# sch_cm4_usb.net
KiCad netlist of a schematic drawn in Altium Designer
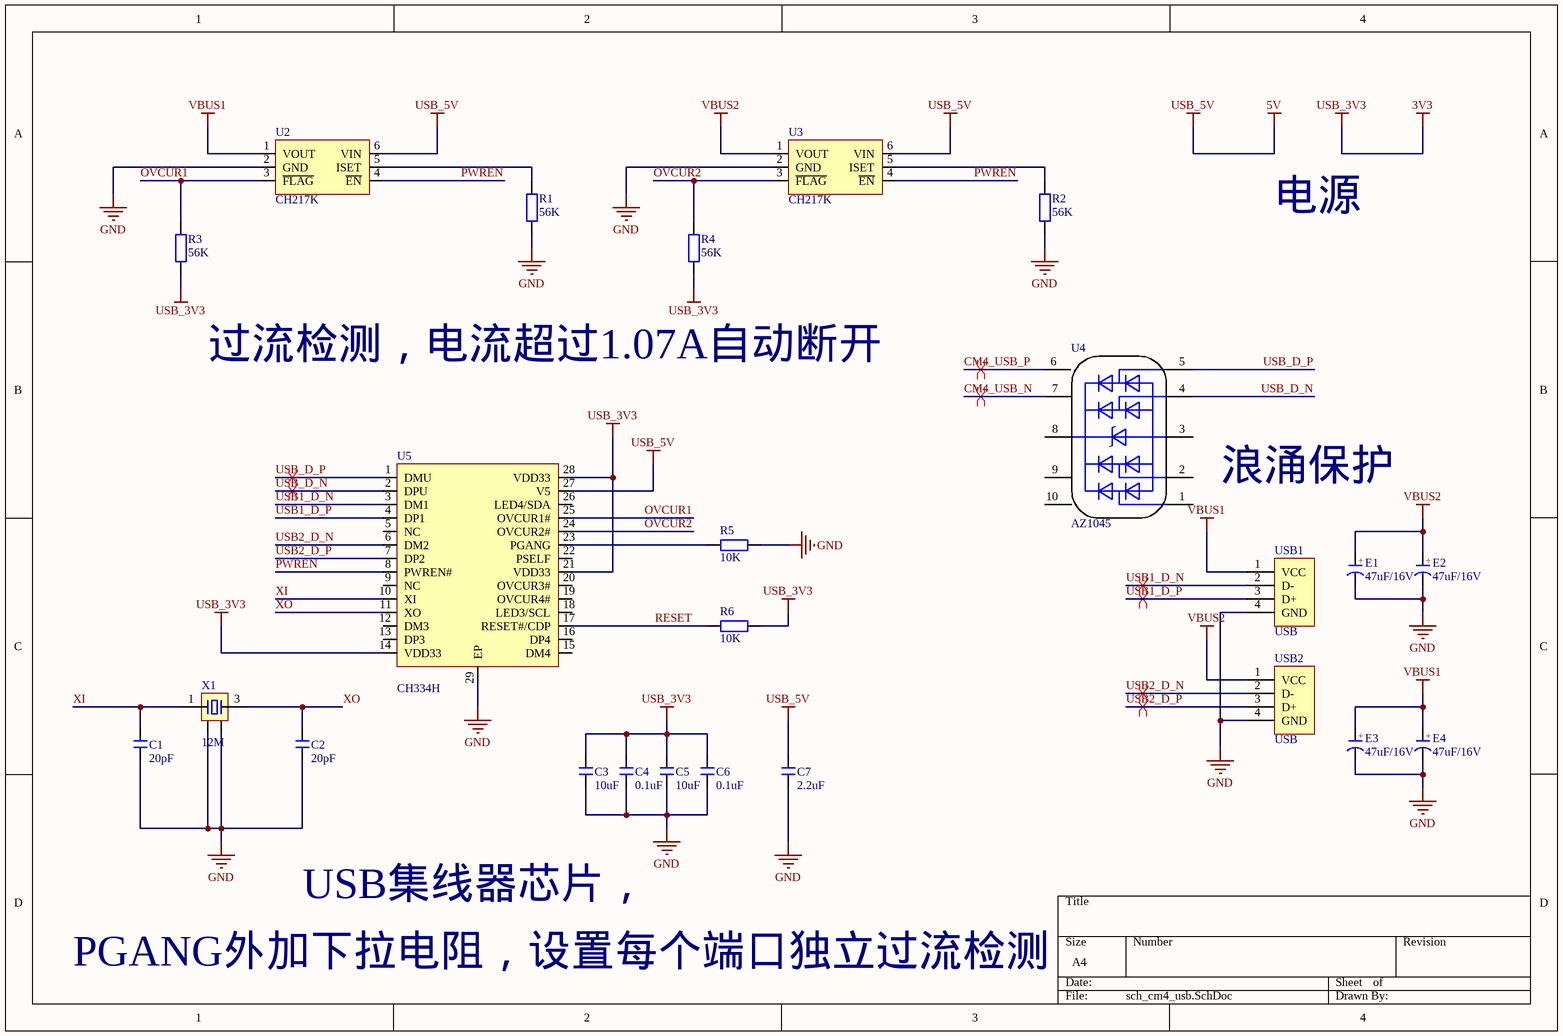
[diagram p0: sch_cm4_usb.SchDoc]

(export (version "E")
  (design (tool "Eeschema 10.0.6"))
  (components
    (comp (ref "C1")
      (value "20pF")
      (footprint "C 0402_L")
      (description "贴片电容")
      (libsource (lib "0.1 - 电阻-电容-电感") (part "C"))
    )
    (comp (ref "C2")
      (value "20pF")
      (footprint "C 0402_L")
      (description "贴片电容")
      (libsource (lib "0.1 - 电阻-电容-电感") (part "C"))
    )
    (comp (ref "C3")
      (value "10uF")
      (footprint "C 0402_L")
      (description "贴片电容")
      (libsource (lib "0.1 - 电阻-电容-电感") (part "C"))
    )
    (comp (ref "C4")
      (value "0.1uF")
      (footprint "C 0402_L")
      (description "贴片电容")
      (libsource (lib "0.1 - 电阻-电容-电感") (part "C"))
    )
    (comp (ref "C5")
      (value "10uF")
      (footprint "C 0402_L")
      (description "贴片电容")
      (libsource (lib "0.1 - 电阻-电容-电感") (part "C"))
    )
    (comp (ref "C6")
      (value "0.1uF")
      (footprint "C 0402_L")
      (description "贴片电容")
      (libsource (lib "0.1 - 电阻-电容-电感") (part "C"))
    )
    (comp (ref "C7")
      (value "2.2uF")
      (footprint "C 0402_L")
      (description "贴片电容")
      (libsource (lib "0.1 - 电阻-电容-电感") (part "C"))
    )
    (comp (ref "E1")
      (value "47uF/16V")
      (footprint "CD B(3528)")
      (description "贴片钽电容")
      (libsource (lib "0.1 - 电阻-电容-电感") (part "CT"))
    )
    (comp (ref "E2")
      (value "47uF/16V")
      (footprint "CD B(3528)")
      (description "贴片钽电容")
      (libsource (lib "0.1 - 电阻-电容-电感") (part "CT"))
    )
    (comp (ref "E3")
      (value "47uF/16V")
      (footprint "CD B(3528)")
      (description "贴片钽电容")
      (libsource (lib "0.1 - 电阻-电容-电感") (part "CT"))
    )
    (comp (ref "E4")
      (value "47uF/16V")
      (footprint "CD B(3528)")
      (description "贴片钽电容")
      (libsource (lib "0.1 - 电阻-电容-电感") (part "CT"))
    )
    (comp (ref "R1")
      (value "56K")
      (footprint "R 0603_L")
      (description "贴片电阻")
      (fields (field (name "版权归属") "来自淘宝 ID：黄晶宝石"))
      (libsource (lib "0.1 - 电阻-电容-电感") (part "R"))
    )
    (comp (ref "R2")
      (value "56K")
      (footprint "R 0603_L")
      (description "贴片电阻")
      (fields (field (name "版权归属") "来自淘宝 ID：黄晶宝石"))
      (libsource (lib "0.1 - 电阻-电容-电感") (part "R"))
    )
    (comp (ref "R3")
      (value "56K")
      (footprint "R 0603_L")
      (description "贴片电阻")
      (fields (field (name "版权归属") "来自淘宝 ID：黄晶宝石"))
      (libsource (lib "0.1 - 电阻-电容-电感") (part "R"))
    )
    (comp (ref "R4")
      (value "56K")
      (footprint "R 0603_L")
      (description "贴片电阻")
      (fields (field (name "版权归属") "来自淘宝 ID：黄晶宝石"))
      (libsource (lib "0.1 - 电阻-电容-电感") (part "R"))
    )
    (comp (ref "R5")
      (value "10K")
      (footprint "R 0402_L")
      (description "贴片电阻")
      (fields (field (name "版权归属") "来自淘宝 ID：黄晶宝石"))
      (libsource (lib "0.1 - 电阻-电容-电感") (part "R"))
    )
    (comp (ref "R6")
      (value "10K")
      (footprint "R 0402_L")
      (description "贴片电阻")
      (fields (field (name "版权归属") "来自淘宝 ID：黄晶宝石"))
      (libsource (lib "0.1 - 电阻-电容-电感") (part "R"))
    )
    (comp (ref "U2") (value "CH217K") (footprint "CH217K") (libsource (lib "schlib_cm4") (part "CH217K")))
    (comp (ref "U3") (value "CH217K") (footprint "CH217K") (libsource (lib "schlib_cm4") (part "CH217K")))
    (comp (ref "U4") (value "AZ1045") (footprint "AZ1045-04F") (libsource (lib "schlib_cm4") (part "AZ1045")))
    (comp (ref "U5")
      (value "CH334H")
      (footprint "CH334H")
      (description "USB集线器")
      (libsource (lib "schlib_cm4") (part "CH334H"))
    )
    (comp (ref "USB1")
      (value "USB")
      (footprint "USB-A/S_F")
      (description "USB-A型母接口")
      (libsource (lib "0.8 - 以太网-音频-USB插座") (part "USB-A/S"))
    )
    (comp (ref "USB2")
      (value "USB")
      (footprint "USB-A/S_F")
      (description "USB-A型母接口")
      (libsource (lib "0.8 - 以太网-音频-USB插座") (part "USB-A/S"))
    )
    (comp (ref "X1")
      (value "12M")
      (footprint "OSC 2025-4P")
      (description "4脚无源晶振")
      (fields (field (name "版权归属") "封装库来自淘宝卖家 ID：黄晶宝石"))
      (libsource (lib "2.0 - 保险丝-晶振-光耦") (part "XTAL-4P"))
    )
  )
  (nets
    (net (code "1") (name "/CM4_USB_N") (class "Default")
      (node (ref "U4") (pin "7") (pinfunction "NC_7") (pintype "passive"))
    )
    (net (code "2") (name "/CM4_USB_P") (class "Default")
      (node (ref "U4") (pin "6") (pinfunction "NC_6") (pintype "passive"))
    )
    (net (code "3") (name "/OVCUR1") (class "Default")
      (node (ref "R3") (pin "2") (pinfunction "2_2") (pintype "passive"))
      (node (ref "U2") (pin "3") (pinfunction "~{FLAG}_3") (pintype "passive"))
      (node (ref "U5") (pin "25") (pinfunction "OVCUR1#_25") (pintype "passive"))
    )
    (net (code "4") (name "/OVCUR2") (class "Default")
      (node (ref "R4") (pin "2") (pinfunction "2_2") (pintype "passive"))
      (node (ref "U3") (pin "3") (pinfunction "~{FLAG}_3") (pintype "passive"))
      (node (ref "U5") (pin "24") (pinfunction "OVCUR2#_24") (pintype "passive"))
    )
    (net (code "5") (name "/PWREN") (class "Default")
      (node (ref "U2") (pin "4") (pinfunction "~{EN}_4") (pintype "passive"))
      (node (ref "U3") (pin "4") (pinfunction "~{EN}_4") (pintype "passive"))
      (node (ref "U5") (pin "8") (pinfunction "PWREN#_8") (pintype "passive"))
    )
    (net (code "6") (name "/RESET") (class "Default")
      (node (ref "R6") (pin "1") (pinfunction "1_1") (pintype "passive"))
      (node (ref "U5") (pin "17") (pinfunction "RESET#/CDP_17") (pintype "passive"))
    )
    (net (code "7") (name "/USB1_D_N") (class "Default")
      (node (ref "U5") (pin "3") (pinfunction "DM1_3") (pintype "passive"))
      (node (ref "USB1") (pin "2") (pinfunction "D-_2") (pintype "passive"))
    )
    (net (code "8") (name "/USB1_D_P") (class "Default")
      (node (ref "U5") (pin "4") (pinfunction "DP1_4") (pintype "passive"))
      (node (ref "USB1") (pin "3") (pinfunction "D+_3") (pintype "passive"))
    )
    (net (code "9") (name "/USB2_D_N") (class "Default")
      (node (ref "U5") (pin "6") (pinfunction "DM2_6") (pintype "passive"))
      (node (ref "USB2") (pin "2") (pinfunction "D-_2") (pintype "passive"))
    )
    (net (code "10") (name "/USB2_D_P") (class "Default")
      (node (ref "U5") (pin "7") (pinfunction "DP2_7") (pintype "passive"))
      (node (ref "USB2") (pin "3") (pinfunction "D+_3") (pintype "passive"))
    )
    (net (code "11") (name "/USB_D_N") (class "Default")
      (node (ref "U4") (pin "4") (pinfunction "I/O_3_4") (pintype "passive"))
      (node (ref "U5") (pin "2") (pinfunction "DPU_2") (pintype "passive"))
    )
    (net (code "12") (name "/USB_D_P") (class "Default")
      (node (ref "U4") (pin "5") (pinfunction "I/O_4_5") (pintype "passive"))
      (node (ref "U5") (pin "1") (pinfunction "DMU_1") (pintype "passive"))
    )
    (net (code "13") (name "/XI") (class "Default")
      (node (ref "C1") (pin "2") (pinfunction "2_2") (pintype "passive"))
      (node (ref "U5") (pin "10") (pinfunction "XI_10") (pintype "passive"))
      (node (ref "X1") (pin "1") (pinfunction "1_1") (pintype "passive"))
    )
    (net (code "14") (name "/XO") (class "Default")
      (node (ref "C2") (pin "2") (pinfunction "2_2") (pintype "passive"))
      (node (ref "U5") (pin "11") (pinfunction "XO_11") (pintype "passive"))
      (node (ref "X1") (pin "3") (pinfunction "3_3") (pintype "passive"))
    )
    (net (code "15") (name "3V3") (class "Default")
      (node (ref "C3") (pin "2") (pinfunction "2_2") (pintype "passive"))
      (node (ref "C4") (pin "2") (pinfunction "2_2") (pintype "passive"))
      (node (ref "C5") (pin "2") (pinfunction "2_2") (pintype "passive"))
      (node (ref "C6") (pin "2") (pinfunction "2_2") (pintype "passive"))
      (node (ref "R3") (pin "1") (pinfunction "1_1") (pintype "passive"))
      (node (ref "R4") (pin "1") (pinfunction "1_1") (pintype "passive"))
      (node (ref "R6") (pin "2") (pinfunction "2_2") (pintype "passive"))
      (node (ref "U5") (pin "14") (pinfunction "VDD33_14") (pintype "passive"))
      (node (ref "U5") (pin "21") (pinfunction "VDD33_21") (pintype "passive"))
      (node (ref "U5") (pin "28") (pinfunction "VDD33_28") (pintype "passive"))
    )
    (net (code "16") (name "5V") (class "Default")
      (node (ref "C7") (pin "2") (pinfunction "2_2") (pintype "passive"))
      (node (ref "U2") (pin "6") (pinfunction "VIN_6") (pintype "passive"))
      (node (ref "U3") (pin "6") (pinfunction "VIN_6") (pintype "passive"))
      (node (ref "U5") (pin "27") (pinfunction "V5_27") (pintype "passive"))
    )
    (net (code "17") (name "GND") (class "Default")
      (node (ref "C1") (pin "1") (pinfunction "1_1") (pintype "passive"))
      (node (ref "C2") (pin "1") (pinfunction "1_1") (pintype "passive"))
      (node (ref "C3") (pin "1") (pinfunction "1_1") (pintype "passive"))
      (node (ref "C4") (pin "1") (pinfunction "1_1") (pintype "passive"))
      (node (ref "C5") (pin "1") (pinfunction "1_1") (pintype "passive"))
      (node (ref "C6") (pin "1") (pinfunction "1_1") (pintype "passive"))
      (node (ref "C7") (pin "1") (pinfunction "1_1") (pintype "passive"))
      (node (ref "E1") (pin "2") (pinfunction "K_2") (pintype "passive"))
      (node (ref "E2") (pin "2") (pinfunction "K_2") (pintype "passive"))
      (node (ref "E3") (pin "2") (pinfunction "K_2") (pintype "passive"))
      (node (ref "E4") (pin "2") (pinfunction "K_2") (pintype "passive"))
      (node (ref "R1") (pin "1") (pinfunction "1_1") (pintype "passive"))
      (node (ref "R2") (pin "1") (pinfunction "1_1") (pintype "passive"))
      (node (ref "R5") (pin "2") (pinfunction "2_2") (pintype "passive"))
      (node (ref "U2") (pin "2") (pinfunction "GND_2") (pintype "passive"))
      (node (ref "U3") (pin "2") (pinfunction "GND_2") (pintype "passive"))
      (node (ref "U5") (pin "29") (pinfunction "EP_29") (pintype "passive"))
      (node (ref "USB1") (pin "4") (pinfunction "GND_4") (pintype "passive"))
      (node (ref "USB2") (pin "4") (pinfunction "GND_4") (pintype "passive"))
      (node (ref "X1") (pin "2") (pinfunction "2_2") (pintype "passive"))
      (node (ref "X1") (pin "4") (pinfunction "4_4") (pintype "passive"))
    )
    (net (code "18") (name "Net-(U2-ISET)") (class "Default")
      (node (ref "R1") (pin "2") (pinfunction "2_2") (pintype "passive"))
      (node (ref "U2") (pin "5") (pinfunction "ISET_5") (pintype "passive"))
    )
    (net (code "19") (name "Net-(U3-ISET)") (class "Default")
      (node (ref "R2") (pin "2") (pinfunction "2_2") (pintype "passive"))
      (node (ref "U3") (pin "5") (pinfunction "ISET_5") (pintype "passive"))
    )
    (net (code "20") (name "Net-(U5-PGANG)") (class "Default")
      (node (ref "R5") (pin "1") (pinfunction "1_1") (pintype "passive"))
      (node (ref "U5") (pin "23") (pinfunction "PGANG_23") (pintype "passive"))
    )
    (net (code "21") (name "VBUS1") (class "Default")
      (node (ref "E3") (pin "1") (pinfunction "A_1") (pintype "passive"))
      (node (ref "E4") (pin "1") (pinfunction "A_1") (pintype "passive"))
      (node (ref "U2") (pin "1") (pinfunction "VOUT_1") (pintype "passive"))
      (node (ref "USB1") (pin "1") (pinfunction "VCC_1") (pintype "passive"))
    )
    (net (code "22") (name "VBUS2") (class "Default")
      (node (ref "E1") (pin "1") (pinfunction "A_1") (pintype "passive"))
      (node (ref "E2") (pin "1") (pinfunction "A_1") (pintype "passive"))
      (node (ref "U3") (pin "1") (pinfunction "VOUT_1") (pintype "passive"))
      (node (ref "USB2") (pin "1") (pinfunction "VCC_1") (pintype "passive"))
    )
    (net (code "23") (name "unconnected-(U4-GND-Pad3)") (class "Default")
      (node (ref "U4") (pin "3") (pinfunction "GND_3") (pintype "passive"))
    )
    (net (code "24") (name "unconnected-(U4-GND-Pad8)") (class "Default")
      (node (ref "U4") (pin "8") (pinfunction "GND_8") (pintype "passive"))
    )
    (net (code "25") (name "unconnected-(U4-I{slash}O_1-Pad1)") (class "Default")
      (node (ref "U4") (pin "1") (pinfunction "I/O_1_1") (pintype "passive"))
    )
    (net (code "26") (name "unconnected-(U4-I{slash}O_2-Pad2)") (class "Default")
      (node (ref "U4") (pin "2") (pinfunction "I/O_2_2") (pintype "passive"))
    )
    (net (code "27") (name "unconnected-(U4-NC-Pad9)") (class "Default")
      (node (ref "U4") (pin "9") (pinfunction "NC_9") (pintype "passive"))
    )
    (net (code "28") (name "unconnected-(U4-NC-Pad10)") (class "Default")
      (node (ref "U4") (pin "10") (pinfunction "NC_10") (pintype "passive"))
    )
    (net (code "29") (name "unconnected-(U5-DM3-Pad12)") (class "Default")
      (node (ref "U5") (pin "12") (pinfunction "DM3_12") (pintype "passive"))
    )
    (net (code "30") (name "unconnected-(U5-DM4-Pad15)") (class "Default")
      (node (ref "U5") (pin "15") (pinfunction "DM4_15") (pintype "passive"))
    )
    (net (code "31") (name "unconnected-(U5-DP3-Pad13)") (class "Default")
      (node (ref "U5") (pin "13") (pinfunction "DP3_13") (pintype "passive"))
    )
    (net (code "32") (name "unconnected-(U5-DP4-Pad16)") (class "Default")
      (node (ref "U5") (pin "16") (pinfunction "DP4_16") (pintype "passive"))
    )
    (net (code "33") (name "unconnected-(U5-LED3{slash}SCL-Pad18)") (class "Default")
      (node (ref "U5") (pin "18") (pinfunction "LED3/SCL_18") (pintype "passive"))
    )
    (net (code "34") (name "unconnected-(U5-LED4{slash}SDA-Pad26)") (class "Default")
      (node (ref "U5") (pin "26") (pinfunction "LED4/SDA_26") (pintype "passive"))
    )
    (net (code "35") (name "unconnected-(U5-NC-Pad5)") (class "Default")
      (node (ref "U5") (pin "5") (pinfunction "NC_5") (pintype "passive"))
    )
    (net (code "36") (name "unconnected-(U5-NC-Pad9)") (class "Default")
      (node (ref "U5") (pin "9") (pinfunction "NC_9") (pintype "passive"))
    )
    (net (code "37") (name "unconnected-(U5-OVCUR3#-Pad20)") (class "Default")
      (node (ref "U5") (pin "20") (pinfunction "OVCUR3#_20") (pintype "passive"))
    )
    (net (code "38") (name "unconnected-(U5-OVCUR4#-Pad19)") (class "Default")
      (node (ref "U5") (pin "19") (pinfunction "OVCUR4#_19") (pintype "passive"))
    )
    (net (code "39") (name "unconnected-(U5-PSELF-Pad22)") (class "Default")
      (node (ref "U5") (pin "22") (pinfunction "PSELF_22") (pintype "passive"))
    )
  )
)
